# USB_Type-C_Test.net
KiCad netlist of a schematic drawn in EAGLE
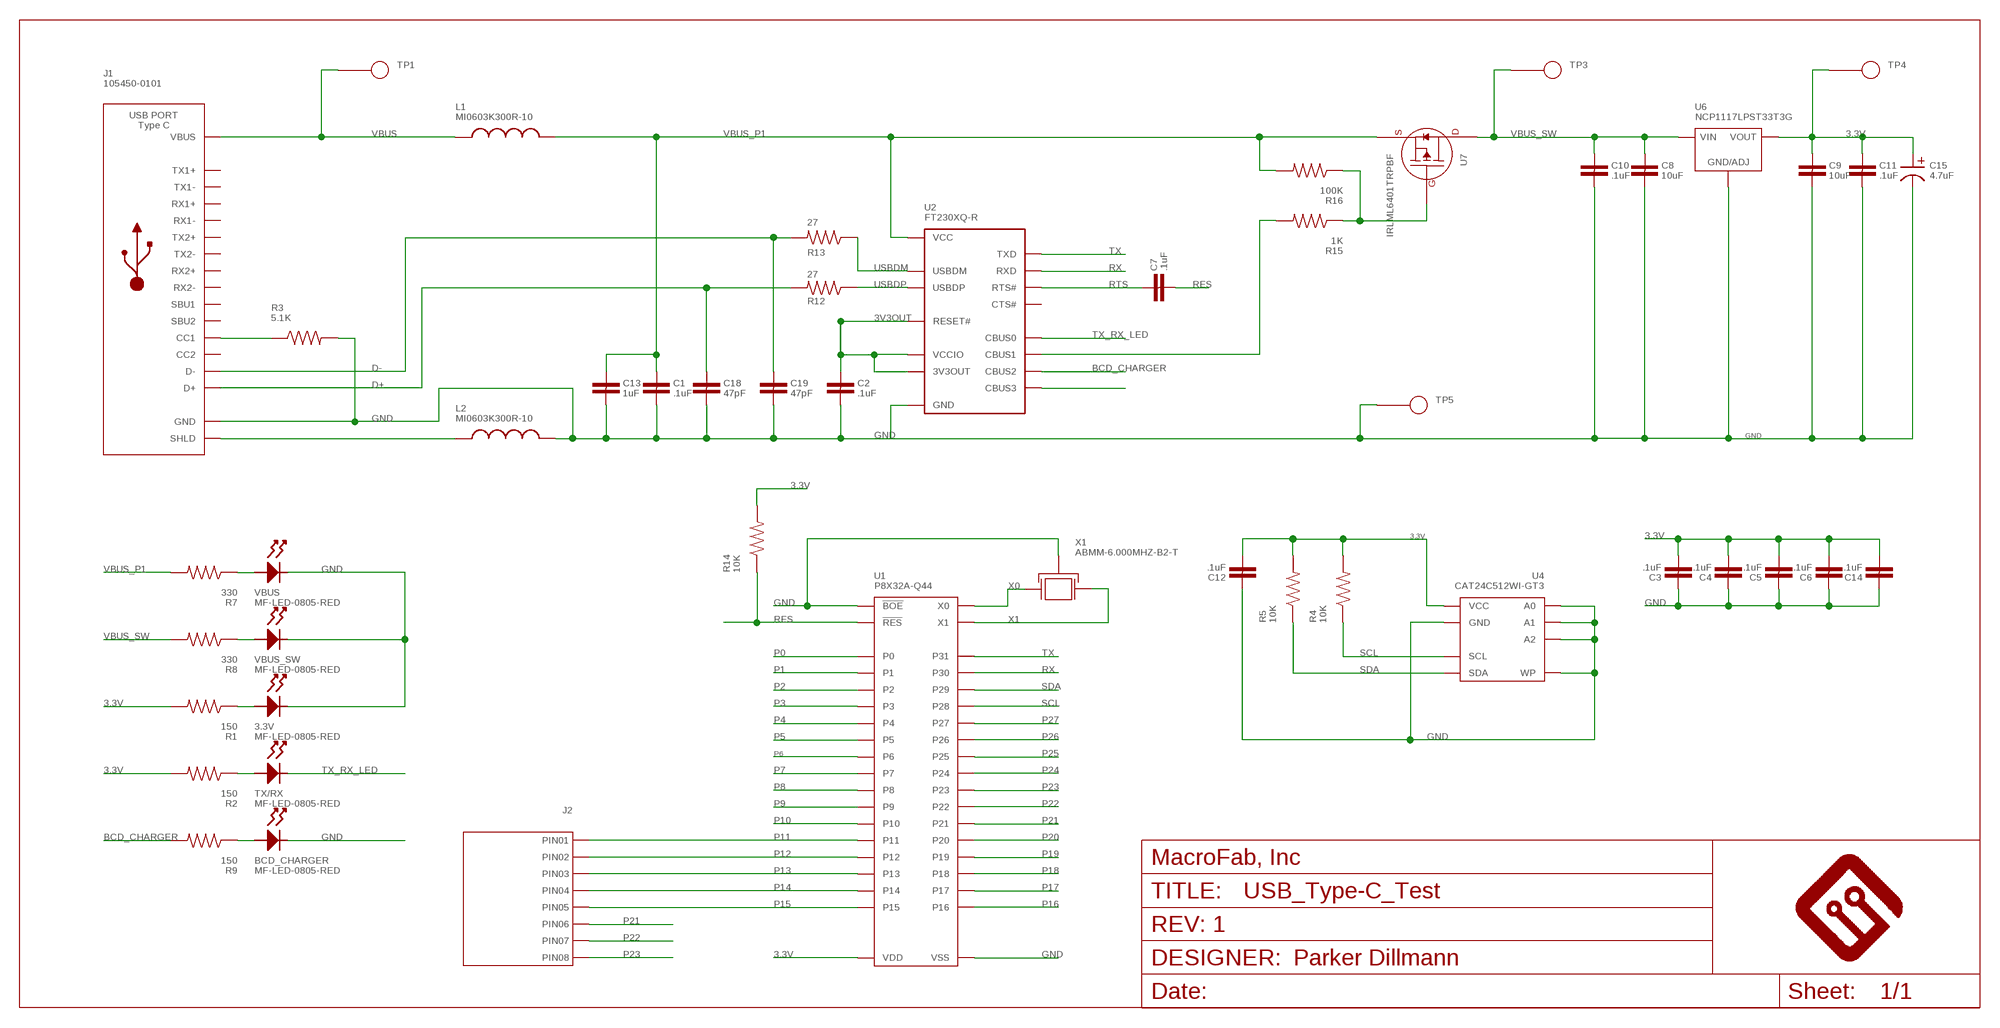
[diagram p0: schematic, sheet 1]

(export (version "E")
  (design (tool "Eeschema 10.0.6"))
  (components
    (comp (ref "3.3V")
      (value "MF-LED-0805-RED")
      (footprint "eagle-import:LED_0805")
      (libsource (lib "eagle-import") (part "LED_SINGLE_0805"))
    )
    (comp (ref "BCD_CHARGER")
      (value "MF-LED-0805-RED")
      (footprint "eagle-import:LED_0805")
      (libsource (lib "eagle-import") (part "LED_SINGLE_0805"))
    )
    (comp (ref "C1")
      (value ".1uF")
      (footprint "eagle-import:0603")
      (libsource (lib "eagle-import") (part "CAPACITOR_NON_POLAR_0603"))
    )
    (comp (ref "C2")
      (value ".1uF")
      (footprint "eagle-import:0603")
      (libsource (lib "eagle-import") (part "CAPACITOR_NON_POLAR_0603"))
    )
    (comp (ref "C3")
      (value ".1uF")
      (footprint "eagle-import:0603")
      (libsource (lib "eagle-import") (part "CAPACITOR_NON_POLAR_0603"))
    )
    (comp (ref "C4")
      (value ".1uF")
      (footprint "eagle-import:0603")
      (libsource (lib "eagle-import") (part "CAPACITOR_NON_POLAR_0603"))
    )
    (comp (ref "C5")
      (value ".1uF")
      (footprint "eagle-import:0603")
      (libsource (lib "eagle-import") (part "CAPACITOR_NON_POLAR_0603"))
    )
    (comp (ref "C6")
      (value ".1uF")
      (footprint "eagle-import:0603")
      (libsource (lib "eagle-import") (part "CAPACITOR_NON_POLAR_0603"))
    )
    (comp (ref "C7")
      (value ".1uF")
      (footprint "eagle-import:0603")
      (libsource (lib "eagle-import") (part "CAPACITOR_NON_POLAR_0603"))
    )
    (comp (ref "C8")
      (value "10uF")
      (footprint "eagle-import:1206")
      (libsource (lib "eagle-import") (part "CAPACITOR_NON_POLAR_1206"))
    )
    (comp (ref "C9")
      (value "10uF")
      (footprint "eagle-import:1206")
      (libsource (lib "eagle-import") (part "CAPACITOR_NON_POLAR_1206"))
    )
    (comp (ref "C10")
      (value ".1uF")
      (footprint "eagle-import:0603")
      (libsource (lib "eagle-import") (part "CAPACITOR_NON_POLAR_0603"))
    )
    (comp (ref "C11")
      (value ".1uF")
      (footprint "eagle-import:0603")
      (libsource (lib "eagle-import") (part "CAPACITOR_NON_POLAR_0603"))
    )
    (comp (ref "C12")
      (value ".1uF")
      (footprint "eagle-import:0603")
      (libsource (lib "eagle-import") (part "CAPACITOR_NON_POLAR_0603"))
    )
    (comp (ref "C13")
      (value "1uF")
      (footprint "eagle-import:0603")
      (libsource (lib "eagle-import") (part "CAPACITOR_NON_POLAR_0603"))
    )
    (comp (ref "C14")
      (value ".1uF")
      (footprint "eagle-import:0603")
      (libsource (lib "eagle-import") (part "CAPACITOR_NON_POLAR_0603"))
    )
    (comp (ref "C15")
      (value "4.7uF")
      (footprint "eagle-import:5MM_CAP_SMD")
      (libsource (lib "eagle-import") (part "CAPACITOR_POLARIZED_5MM_SMD"))
    )
    (comp (ref "C18")
      (value "47pF")
      (footprint "eagle-import:0603")
      (libsource (lib "eagle-import") (part "CAPACITOR_NON_POLAR_0603"))
    )
    (comp (ref "C19")
      (value "47pF")
      (footprint "eagle-import:0603")
      (libsource (lib "eagle-import") (part "CAPACITOR_NON_POLAR_0603"))
    )
    (comp (ref "FRAME1")
      (value "MF_FRAMEDEFAULT")
      (footprint "eagle-import:MF_FRAME_DEFAULT")
      (fields
        (field (name "HOUSEPART") "0")
        (field (name "DNAME") "Parker Dillmann")
        (field (name "REVNUM") "REV: 1")
      )
      (libsource (lib "eagle-import") (part "MF_FRAMEDEFAULT"))
    )
    (comp (ref "J1")
      (value "105450-0101")
      (footprint "eagle-import:105450-0101")
      (fields (field (name "MPN") "105450-0101"))
      (libsource (lib "eagle-import") (part "USB_TYPE-C_105450-0101"))
    )
    (comp (ref "J2")
      (value "CON_01X08_2.54MM_PIN_HEADER")
      (footprint "eagle-import:2.54MM_01X08_PIN_HEADER")
      (libsource (lib "eagle-import") (part "CON_01X08_2.54MM_PIN_HEADER"))
    )
    (comp (ref "L1")
      (value "MI0603K300R-10")
      (footprint "eagle-import:0603")
      (libsource (lib "eagle-import") (part "INDUCTOR_0603"))
    )
    (comp (ref "L2")
      (value "MI0603K300R-10")
      (footprint "eagle-import:0603")
      (libsource (lib "eagle-import") (part "INDUCTOR_0603"))
    )
    (comp (ref "R1")
      (value "150")
      (footprint "eagle-import:0603")
      (libsource (lib "eagle-import") (part "RESISTOR_0603"))
    )
    (comp (ref "R2")
      (value "150")
      (footprint "eagle-import:0603")
      (libsource (lib "eagle-import") (part "RESISTOR_0603"))
    )
    (comp (ref "R3")
      (value "5.1K")
      (footprint "eagle-import:0603")
      (libsource (lib "eagle-import") (part "RESISTOR_0603"))
    )
    (comp (ref "R4")
      (value "10K")
      (footprint "eagle-import:0603")
      (libsource (lib "eagle-import") (part "RESISTOR_0603"))
    )
    (comp (ref "R5")
      (value "10K")
      (footprint "eagle-import:0603")
      (libsource (lib "eagle-import") (part "RESISTOR_0603"))
    )
    (comp (ref "R7")
      (value "330")
      (footprint "eagle-import:0603")
      (libsource (lib "eagle-import") (part "RESISTOR_0603"))
    )
    (comp (ref "R8")
      (value "330")
      (footprint "eagle-import:0603")
      (libsource (lib "eagle-import") (part "RESISTOR_0603"))
    )
    (comp (ref "R9")
      (value "150")
      (footprint "eagle-import:0603")
      (libsource (lib "eagle-import") (part "RESISTOR_0603"))
    )
    (comp (ref "R12")
      (value "27")
      (footprint "eagle-import:0603")
      (libsource (lib "eagle-import") (part "RESISTOR_0603"))
    )
    (comp (ref "R13")
      (value "27")
      (footprint "eagle-import:0603")
      (libsource (lib "eagle-import") (part "RESISTOR_0603"))
    )
    (comp (ref "R14")
      (value "10K")
      (footprint "eagle-import:0603")
      (libsource (lib "eagle-import") (part "RESISTOR_0603"))
    )
    (comp (ref "R15")
      (value "1K")
      (footprint "eagle-import:0603")
      (libsource (lib "eagle-import") (part "RESISTOR_0603"))
    )
    (comp (ref "R16")
      (value "100K")
      (footprint "eagle-import:0603")
      (libsource (lib "eagle-import") (part "RESISTOR_0603"))
    )
    (comp (ref "TP1")
      (value "TEST_POINT_SINGLE_KEYSTONE_5115-5119")
      (footprint "eagle-import:KEYSTONE_5115-5119")
      (libsource (lib "eagle-import") (part "TEST_POINT_SINGLE_KEYSTONE_5115-5119"))
    )
    (comp (ref "TP3")
      (value "TEST_POINT_SINGLE_KEYSTONE_5115-5119")
      (footprint "eagle-import:KEYSTONE_5115-5119")
      (libsource (lib "eagle-import") (part "TEST_POINT_SINGLE_KEYSTONE_5115-5119"))
    )
    (comp (ref "TP4")
      (value "TEST_POINT_SINGLE_KEYSTONE_5115-5119")
      (footprint "eagle-import:KEYSTONE_5115-5119")
      (libsource (lib "eagle-import") (part "TEST_POINT_SINGLE_KEYSTONE_5115-5119"))
    )
    (comp (ref "TP5")
      (value "TEST_POINT_SINGLE_KEYSTONE_5115-5119")
      (footprint "eagle-import:KEYSTONE_5115-5119")
      (libsource (lib "eagle-import") (part "TEST_POINT_SINGLE_KEYSTONE_5115-5119"))
    )
    (comp (ref "TX/RX")
      (value "MF-LED-0805-RED")
      (footprint "eagle-import:LED_0805")
      (libsource (lib "eagle-import") (part "LED_SINGLE_0805"))
    )
    (comp (ref "U1")
      (value "P8X32A-Q44")
      (footprint "eagle-import:P8X32A_LQFP-44")
      (libsource (lib "eagle-import") (part "P8X32A-Q44"))
    )
    (comp (ref "U2")
      (value "FT230XQ-R")
      (footprint "eagle-import:FT230X_QFN-16")
      (libsource (lib "eagle-import") (part "FT230XQ"))
    )
    (comp (ref "U4")
      (value "CAT24C512WI-GT3")
      (footprint "eagle-import:SOIC-8_W")
      (libsource (lib "eagle-import") (part "EEPROM_I2CSOIC-8_W"))
    )
    (comp (ref "U6")
      (value "NCP1117LPST33T3G")
      (footprint "eagle-import:SOT-223-3")
      (fields (field (name "HOUSEPART") "NO"))
      (libsource (lib "eagle-import") (part "NCP1117LPST33T3G"))
    )
    (comp (ref "U7")
      (value "IRLML6401TRPBF")
      (footprint "eagle-import:SOT-23-3")
      (libsource (lib "eagle-import") (part "MOSFET_P-CHANNEL_SINGLE_SOT-23"))
    )
    (comp (ref "VBUS")
      (value "MF-LED-0805-RED")
      (footprint "eagle-import:LED_0805")
      (libsource (lib "eagle-import") (part "LED_SINGLE_0805"))
    )
    (comp (ref "VBUS_SW")
      (value "MF-LED-0805-RED")
      (footprint "eagle-import:LED_0805")
      (libsource (lib "eagle-import") (part "LED_SINGLE_0805"))
    )
    (comp (ref "X1")
      (value "ABMM-6.000MHZ-B2-T")
      (footprint "eagle-import:7MMX5MM")
      (fields (field (name "HOUSEPART") "NO"))
      (libsource (lib "eagle-import") (part "CYRSTAL_GND_ABMM"))
    )
  )
  (nets
    (net (code "1") (name "/3.3V") (class "Default")
      (node (ref "C11") (pin "1") (pinfunction "1_1") (pintype "passive"))
      (node (ref "C12") (pin "2") (pinfunction "2_2") (pintype "passive"))
      (node (ref "C14") (pin "2") (pinfunction "2_2") (pintype "passive"))
      (node (ref "C15") (pin "P") (pinfunction "POS_P") (pintype "bidirectional"))
      (node (ref "C3") (pin "2") (pinfunction "2_2") (pintype "passive"))
      (node (ref "C4") (pin "2") (pinfunction "2_2") (pintype "passive"))
      (node (ref "C5") (pin "2") (pinfunction "2_2") (pintype "passive"))
      (node (ref "C6") (pin "2") (pinfunction "2_2") (pintype "passive"))
      (node (ref "C9") (pin "1") (pinfunction "1_1") (pintype "passive"))
      (node (ref "R1") (pin "2") (pinfunction "2_2") (pintype "passive"))
      (node (ref "R14") (pin "2") (pinfunction "2_2") (pintype "passive"))
      (node (ref "R2") (pin "2") (pinfunction "2_2") (pintype "passive"))
      (node (ref "R4") (pin "2") (pinfunction "2_2") (pintype "passive"))
      (node (ref "R5") (pin "2") (pinfunction "2_2") (pintype "passive"))
      (node (ref "TP4") (pin "P$1") (pinfunction "P$1_P$1") (pintype "bidirectional"))
      (node (ref "U1") (pin "18") (pinfunction "VDD_18") (pintype "bidirectional"))
      (node (ref "U1") (pin "30") (pinfunction "VDD_30") (pintype "bidirectional"))
      (node (ref "U1") (pin "40") (pinfunction "VDD_40") (pintype "bidirectional"))
      (node (ref "U1") (pin "8") (pinfunction "VDD_8") (pintype "bidirectional"))
      (node (ref "U4") (pin "8") (pinfunction "VCC_8") (pintype "bidirectional"))
      (node (ref "U6") (pin "P$1") (pinfunction "VOUT_P$1") (pintype "bidirectional"))
      (node (ref "U6") (pin "P$3") (pinfunction "VOUT_P$3") (pintype "bidirectional"))
    )
    (net (code "2") (name "/3V3OUT") (class "Default")
      (node (ref "C2") (pin "1") (pinfunction "1_1") (pintype "passive"))
      (node (ref "U2") (pin "1") (pinfunction "VCCIO_1") (pintype "bidirectional"))
      (node (ref "U2") (pin "8") (pinfunction "3V3OUT_8") (pintype "bidirectional"))
      (node (ref "U2") (pin "9") (pinfunction "RESET#_9") (pintype "bidirectional"))
    )
    (net (code "3") (name "/BCD_CHARGER") (class "Default")
      (node (ref "R9") (pin "2") (pinfunction "2_2") (pintype "passive"))
      (node (ref "U2") (pin "5") (pinfunction "CBUS2_5") (pintype "bidirectional"))
    )
    (net (code "4") (name "/D+") (class "Default")
      (node (ref "C18") (pin "1") (pinfunction "1_1") (pintype "passive"))
      (node (ref "J1") (pin "A6") (pinfunction "D+_A6") (pintype "bidirectional"))
      (node (ref "J1") (pin "B6") (pinfunction "D+_B6") (pintype "bidirectional"))
      (node (ref "R12") (pin "2") (pinfunction "2_2") (pintype "passive"))
    )
    (net (code "5") (name "/D-") (class "Default")
      (node (ref "C19") (pin "1") (pinfunction "1_1") (pintype "passive"))
      (node (ref "J1") (pin "A7") (pinfunction "D-_A7") (pintype "bidirectional"))
      (node (ref "J1") (pin "B7") (pinfunction "D-_B7") (pintype "bidirectional"))
      (node (ref "R13") (pin "2") (pinfunction "2_2") (pintype "passive"))
    )
    (net (code "6") (name "/GND") (class "Default")
      (node (ref "3.3V") (pin "CATHODE") (pinfunction "CATHODE_CATHODE") (pintype "bidirectional"))
      (node (ref "BCD_CHARGER") (pin "CATHODE") (pinfunction "CATHODE_CATHODE") (pintype "bidirectional"))
      (node (ref "C1") (pin "2") (pinfunction "2_2") (pintype "passive"))
      (node (ref "C10") (pin "2") (pinfunction "2_2") (pintype "passive"))
      (node (ref "C11") (pin "2") (pinfunction "2_2") (pintype "passive"))
      (node (ref "C12") (pin "1") (pinfunction "1_1") (pintype "passive"))
      (node (ref "C13") (pin "2") (pinfunction "2_2") (pintype "passive"))
      (node (ref "C14") (pin "1") (pinfunction "1_1") (pintype "passive"))
      (node (ref "C15") (pin "N") (pinfunction "NEG_N") (pintype "bidirectional"))
      (node (ref "C18") (pin "2") (pinfunction "2_2") (pintype "passive"))
      (node (ref "C19") (pin "2") (pinfunction "2_2") (pintype "passive"))
      (node (ref "C2") (pin "2") (pinfunction "2_2") (pintype "passive"))
      (node (ref "C3") (pin "1") (pinfunction "1_1") (pintype "passive"))
      (node (ref "C4") (pin "1") (pinfunction "1_1") (pintype "passive"))
      (node (ref "C5") (pin "1") (pinfunction "1_1") (pintype "passive"))
      (node (ref "C6") (pin "1") (pinfunction "1_1") (pintype "passive"))
      (node (ref "C8") (pin "2") (pinfunction "2_2") (pintype "passive"))
      (node (ref "C9") (pin "2") (pinfunction "2_2") (pintype "passive"))
      (node (ref "J1") (pin "A1") (pinfunction "GND_A1") (pintype "bidirectional"))
      (node (ref "J1") (pin "A12") (pinfunction "GND_A12") (pintype "bidirectional"))
      (node (ref "J1") (pin "B1") (pinfunction "GND_B1") (pintype "bidirectional"))
      (node (ref "J1") (pin "B12") (pinfunction "GND_B12") (pintype "bidirectional"))
      (node (ref "L2") (pin "2") (pinfunction "P$2_2") (pintype "bidirectional"))
      (node (ref "R3") (pin "2") (pinfunction "2_2") (pintype "passive"))
      (node (ref "TP5") (pin "P$1") (pinfunction "P$1_P$1") (pintype "bidirectional"))
      (node (ref "U1") (pin "17") (pinfunction "VSS_17") (pintype "bidirectional"))
      (node (ref "U1") (pin "27") (pinfunction "VSS_27") (pintype "bidirectional"))
      (node (ref "U1") (pin "39") (pinfunction "VSS_39") (pintype "bidirectional"))
      (node (ref "U1") (pin "5") (pinfunction "VSS_5") (pintype "bidirectional"))
      (node (ref "U1") (pin "6") (pinfunction "~{BOE}_6") (pintype "bidirectional"))
      (node (ref "U2") (pin "13") (pinfunction "GND_13") (pintype "bidirectional"))
      (node (ref "U2") (pin "3") (pinfunction "GND_3") (pintype "bidirectional"))
      (node (ref "U2") (pin "PAD") (pinfunction "GND_PAD") (pintype "bidirectional"))
      (node (ref "U4") (pin "1") (pinfunction "A0_1") (pintype "bidirectional"))
      (node (ref "U4") (pin "2") (pinfunction "A1_2") (pintype "bidirectional"))
      (node (ref "U4") (pin "3") (pinfunction "A2_3") (pintype "bidirectional"))
      (node (ref "U4") (pin "4") (pinfunction "GND_4") (pintype "bidirectional"))
      (node (ref "U4") (pin "7") (pinfunction "WP_7") (pintype "bidirectional"))
      (node (ref "U6") (pin "P$2") (pinfunction "GND/ADJ_P$2") (pintype "bidirectional"))
      (node (ref "VBUS") (pin "CATHODE") (pinfunction "CATHODE_CATHODE") (pintype "bidirectional"))
      (node (ref "VBUS_SW") (pin "CATHODE") (pinfunction "CATHODE_CATHODE") (pintype "bidirectional"))
      (node (ref "X1") (pin "P$2") (pinfunction "GND_P$2") (pintype "bidirectional"))
      (node (ref "X1") (pin "P$4") (pinfunction "GND_P$4") (pintype "bidirectional"))
    )
    (net (code "7") (name "/P0") (class "Default")
      (node (ref "U1") (pin "41") (pinfunction "P0_41") (pintype "bidirectional"))
    )
    (net (code "8") (name "/P1") (class "Default")
      (node (ref "U1") (pin "42") (pinfunction "P1_42") (pintype "bidirectional"))
    )
    (net (code "9") (name "/P2") (class "Default")
      (node (ref "U1") (pin "43") (pinfunction "P2_43") (pintype "bidirectional"))
    )
    (net (code "10") (name "/P3") (class "Default")
      (node (ref "U1") (pin "44") (pinfunction "P3_44") (pintype "bidirectional"))
    )
    (net (code "11") (name "/P4") (class "Default")
      (node (ref "U1") (pin "1") (pinfunction "P4_1") (pintype "bidirectional"))
    )
    (net (code "12") (name "/P5") (class "Default")
      (node (ref "U1") (pin "2") (pinfunction "P5_2") (pintype "bidirectional"))
    )
    (net (code "13") (name "/P6") (class "Default")
      (node (ref "U1") (pin "3") (pinfunction "P6_3") (pintype "bidirectional"))
    )
    (net (code "14") (name "/P7") (class "Default")
      (node (ref "U1") (pin "4") (pinfunction "P7_4") (pintype "bidirectional"))
    )
    (net (code "15") (name "/P8") (class "Default")
      (node (ref "U1") (pin "9") (pinfunction "P8_9") (pintype "bidirectional"))
    )
    (net (code "16") (name "/P9") (class "Default")
      (node (ref "U1") (pin "10") (pinfunction "P9_10") (pintype "bidirectional"))
    )
    (net (code "17") (name "/P10") (class "Default")
      (node (ref "U1") (pin "11") (pinfunction "P10_11") (pintype "bidirectional"))
    )
    (net (code "18") (name "/P11") (class "Default")
      (node (ref "J2") (pin "1") (pinfunction "1_1") (pintype "bidirectional"))
      (node (ref "U1") (pin "12") (pinfunction "P11_12") (pintype "bidirectional"))
    )
    (net (code "19") (name "/P12") (class "Default")
      (node (ref "J2") (pin "2") (pinfunction "2_2") (pintype "bidirectional"))
      (node (ref "U1") (pin "13") (pinfunction "P12_13") (pintype "bidirectional"))
    )
    (net (code "20") (name "/P13") (class "Default")
      (node (ref "J2") (pin "3") (pinfunction "3_3") (pintype "bidirectional"))
      (node (ref "U1") (pin "14") (pinfunction "P13_14") (pintype "bidirectional"))
    )
    (net (code "21") (name "/P14") (class "Default")
      (node (ref "J2") (pin "4") (pinfunction "4_4") (pintype "bidirectional"))
      (node (ref "U1") (pin "15") (pinfunction "P14_15") (pintype "bidirectional"))
    )
    (net (code "22") (name "/P15") (class "Default")
      (node (ref "J2") (pin "5") (pinfunction "5_5") (pintype "bidirectional"))
      (node (ref "U1") (pin "16") (pinfunction "P15_16") (pintype "bidirectional"))
    )
    (net (code "23") (name "/P16") (class "Default")
      (node (ref "U1") (pin "19") (pinfunction "P16_19") (pintype "bidirectional"))
    )
    (net (code "24") (name "/P17") (class "Default")
      (node (ref "U1") (pin "20") (pinfunction "P17_20") (pintype "bidirectional"))
    )
    (net (code "25") (name "/P18") (class "Default")
      (node (ref "U1") (pin "21") (pinfunction "P18_21") (pintype "bidirectional"))
    )
    (net (code "26") (name "/P19") (class "Default")
      (node (ref "U1") (pin "22") (pinfunction "P19_22") (pintype "bidirectional"))
    )
    (net (code "27") (name "/P20") (class "Default")
      (node (ref "U1") (pin "23") (pinfunction "P20_23") (pintype "bidirectional"))
    )
    (net (code "28") (name "/P21") (class "Default")
      (node (ref "J2") (pin "6") (pinfunction "6_6") (pintype "bidirectional"))
      (node (ref "U1") (pin "24") (pinfunction "P21_24") (pintype "bidirectional"))
    )
    (net (code "29") (name "/P22") (class "Default")
      (node (ref "J2") (pin "7") (pinfunction "7_7") (pintype "bidirectional"))
      (node (ref "U1") (pin "25") (pinfunction "P22_25") (pintype "bidirectional"))
    )
    (net (code "30") (name "/P23") (class "Default")
      (node (ref "J2") (pin "8") (pinfunction "8_8") (pintype "bidirectional"))
      (node (ref "U1") (pin "26") (pinfunction "P23_26") (pintype "bidirectional"))
    )
    (net (code "31") (name "/P24") (class "Default")
      (node (ref "U1") (pin "31") (pinfunction "P24_31") (pintype "bidirectional"))
    )
    (net (code "32") (name "/P25") (class "Default")
      (node (ref "U1") (pin "32") (pinfunction "P25_32") (pintype "bidirectional"))
    )
    (net (code "33") (name "/P26") (class "Default")
      (node (ref "U1") (pin "33") (pinfunction "P26_33") (pintype "bidirectional"))
    )
    (net (code "34") (name "/P27") (class "Default")
      (node (ref "U1") (pin "34") (pinfunction "P27_34") (pintype "bidirectional"))
    )
    (net (code "35") (name "/RES") (class "Default")
      (node (ref "C7") (pin "2") (pinfunction "2_2") (pintype "passive"))
      (node (ref "R14") (pin "1") (pinfunction "1_1") (pintype "passive"))
      (node (ref "U1") (pin "7") (pinfunction "~{RES}_7") (pintype "bidirectional"))
    )
    (net (code "36") (name "/RTS") (class "Default")
      (node (ref "C7") (pin "1") (pinfunction "1_1") (pintype "passive"))
      (node (ref "U2") (pin "16") (pinfunction "RTS#_16") (pintype "bidirectional"))
    )
    (net (code "37") (name "/RX") (class "Default")
      (node (ref "U1") (pin "37") (pinfunction "P30_37") (pintype "bidirectional"))
      (node (ref "U2") (pin "2") (pinfunction "RXD_2") (pintype "bidirectional"))
    )
    (net (code "38") (name "/SCL") (class "Default")
      (node (ref "R4") (pin "1") (pinfunction "1_1") (pintype "passive"))
      (node (ref "U1") (pin "35") (pinfunction "P28_35") (pintype "bidirectional"))
      (node (ref "U4") (pin "6") (pinfunction "SCL_6") (pintype "bidirectional"))
    )
    (net (code "39") (name "/SDA") (class "Default")
      (node (ref "R5") (pin "1") (pinfunction "1_1") (pintype "passive"))
      (node (ref "U1") (pin "36") (pinfunction "P29_36") (pintype "bidirectional"))
      (node (ref "U4") (pin "5") (pinfunction "SDA_5") (pintype "bidirectional"))
    )
    (net (code "40") (name "/TX") (class "Default")
      (node (ref "U1") (pin "38") (pinfunction "P31_38") (pintype "bidirectional"))
      (node (ref "U2") (pin "15") (pinfunction "TXD_15") (pintype "bidirectional"))
    )
    (net (code "41") (name "/TX_RX_LED") (class "Default")
      (node (ref "TX/RX") (pin "CATHODE") (pinfunction "CATHODE_CATHODE") (pintype "bidirectional"))
      (node (ref "U2") (pin "12") (pinfunction "CBUS0_12") (pintype "bidirectional"))
    )
    (net (code "42") (name "/USBDM") (class "Default")
      (node (ref "R13") (pin "1") (pinfunction "1_1") (pintype "passive"))
      (node (ref "U2") (pin "7") (pinfunction "USBDM_7") (pintype "bidirectional"))
    )
    (net (code "43") (name "/USBDP") (class "Default")
      (node (ref "R12") (pin "1") (pinfunction "1_1") (pintype "passive"))
      (node (ref "U2") (pin "6") (pinfunction "USBDP_6") (pintype "bidirectional"))
    )
    (net (code "44") (name "/VBUS") (class "Default")
      (node (ref "J1") (pin "A4") (pinfunction "VBUS_A4") (pintype "bidirectional"))
      (node (ref "J1") (pin "A9") (pinfunction "VBUS_A9") (pintype "bidirectional"))
      (node (ref "J1") (pin "B4") (pinfunction "VBUS_B4") (pintype "bidirectional"))
      (node (ref "J1") (pin "B9") (pinfunction "VBUS_B9") (pintype "bidirectional"))
      (node (ref "L1") (pin "1") (pinfunction "P$1_1") (pintype "bidirectional"))
      (node (ref "TP1") (pin "P$1") (pinfunction "P$1_P$1") (pintype "bidirectional"))
    )
    (net (code "45") (name "/VBUS_P1") (class "Default")
      (node (ref "C1") (pin "1") (pinfunction "1_1") (pintype "passive"))
      (node (ref "C13") (pin "1") (pinfunction "1_1") (pintype "passive"))
      (node (ref "L1") (pin "2") (pinfunction "P$2_2") (pintype "bidirectional"))
      (node (ref "R16") (pin "2") (pinfunction "2_2") (pintype "passive"))
      (node (ref "R7") (pin "2") (pinfunction "2_2") (pintype "passive"))
      (node (ref "U2") (pin "10") (pinfunction "VCC_10") (pintype "bidirectional"))
      (node (ref "U7") (pin "2") (pinfunction "SOURCE_2") (pintype "bidirectional"))
    )
    (net (code "46") (name "/VBUS_SW") (class "Default")
      (node (ref "C10") (pin "1") (pinfunction "1_1") (pintype "passive"))
      (node (ref "C8") (pin "1") (pinfunction "1_1") (pintype "passive"))
      (node (ref "R8") (pin "2") (pinfunction "2_2") (pintype "passive"))
      (node (ref "TP3") (pin "P$1") (pinfunction "P$1_P$1") (pintype "bidirectional"))
      (node (ref "U6") (pin "P$4") (pinfunction "VIN_P$4") (pintype "bidirectional"))
      (node (ref "U7") (pin "3") (pinfunction "DRAIN_3") (pintype "bidirectional"))
    )
    (net (code "47") (name "/X0") (class "Default")
      (node (ref "U1") (pin "29") (pinfunction "X0_29") (pintype "bidirectional"))
      (node (ref "X1") (pin "P$3") (pinfunction "X1_P$3") (pintype "bidirectional"))
    )
    (net (code "48") (name "/X1") (class "Default")
      (node (ref "U1") (pin "28") (pinfunction "X1_28") (pintype "bidirectional"))
      (node (ref "X1") (pin "P$1") (pinfunction "X0_P$1") (pintype "bidirectional"))
    )
    (net (code "49") (name "Net-(3.3V-PadANODE)") (class "Default")
      (node (ref "3.3V") (pin "ANODE") (pinfunction "ANODE_ANODE") (pintype "bidirectional"))
      (node (ref "R1") (pin "1") (pinfunction "1_1") (pintype "passive"))
    )
    (net (code "50") (name "Net-(BCD_CHARGER-PadANODE)") (class "Default")
      (node (ref "BCD_CHARGER") (pin "ANODE") (pinfunction "ANODE_ANODE") (pintype "bidirectional"))
      (node (ref "R9") (pin "1") (pinfunction "1_1") (pintype "passive"))
    )
    (net (code "51") (name "Net-(J1-CC1)") (class "Default")
      (node (ref "J1") (pin "A5") (pinfunction "CC1_A5") (pintype "bidirectional"))
      (node (ref "R3") (pin "1") (pinfunction "1_1") (pintype "passive"))
    )
    (net (code "52") (name "Net-(L2-P$1)") (class "Default")
      (node (ref "J1") (pin "S_T1") (pinfunction "SHLD_S_T1") (pintype "bidirectional"))
      (node (ref "J1") (pin "S_T2") (pinfunction "SHLD_S_T2") (pintype "bidirectional"))
      (node (ref "J1") (pin "S_T3") (pinfunction "SHLD_S_T3") (pintype "bidirectional"))
      (node (ref "J1") (pin "S_T4") (pinfunction "SHLD_S_T4") (pintype "bidirectional"))
      (node (ref "L2") (pin "1") (pinfunction "P$1_1") (pintype "bidirectional"))
    )
    (net (code "53") (name "Net-(R2-Pad1)") (class "Default")
      (node (ref "R2") (pin "1") (pinfunction "1_1") (pintype "passive"))
      (node (ref "TX/RX") (pin "ANODE") (pinfunction "ANODE_ANODE") (pintype "bidirectional"))
    )
    (net (code "54") (name "Net-(R7-Pad1)") (class "Default")
      (node (ref "R7") (pin "1") (pinfunction "1_1") (pintype "passive"))
      (node (ref "VBUS") (pin "ANODE") (pinfunction "ANODE_ANODE") (pintype "bidirectional"))
    )
    (net (code "55") (name "Net-(R8-Pad1)") (class "Default")
      (node (ref "R8") (pin "1") (pinfunction "1_1") (pintype "passive"))
      (node (ref "VBUS_SW") (pin "ANODE") (pinfunction "ANODE_ANODE") (pintype "bidirectional"))
    )
    (net (code "56") (name "Net-(U2-CBUS1)") (class "Default")
      (node (ref "R15") (pin "2") (pinfunction "2_2") (pintype "passive"))
      (node (ref "U2") (pin "11") (pinfunction "CBUS1_11") (pintype "bidirectional"))
    )
    (net (code "57") (name "Net-(U7-GATE)") (class "Default")
      (node (ref "R15") (pin "1") (pinfunction "1_1") (pintype "passive"))
      (node (ref "R16") (pin "1") (pinfunction "1_1") (pintype "passive"))
      (node (ref "U7") (pin "1") (pinfunction "GATE_1") (pintype "bidirectional"))
    )
    (net (code "58") (name "unconnected-(J1-CC2-PadB5)") (class "Default")
      (node (ref "J1") (pin "B5") (pinfunction "CC2_B5") (pintype "bidirectional"))
    )
    (net (code "59") (name "unconnected-(J1-RX1+-PadB11)") (class "Default")
      (node (ref "J1") (pin "B11") (pinfunction "RX1+_B11") (pintype "bidirectional"))
    )
    (net (code "60") (name "unconnected-(J1-RX1--PadB10)") (class "Default")
      (node (ref "J1") (pin "B10") (pinfunction "RX1-_B10") (pintype "bidirectional"))
    )
    (net (code "61") (name "unconnected-(J1-RX2+-PadA11)") (class "Default")
      (node (ref "J1") (pin "A11") (pinfunction "RX2+_A11") (pintype "bidirectional"))
    )
    (net (code "62") (name "unconnected-(J1-RX2--PadA10)") (class "Default")
      (node (ref "J1") (pin "A10") (pinfunction "RX2-_A10") (pintype "bidirectional"))
    )
    (net (code "63") (name "unconnected-(J1-SBU1-PadA8)") (class "Default")
      (node (ref "J1") (pin "A8") (pinfunction "SBU1_A8") (pintype "bidirectional"))
    )
    (net (code "64") (name "unconnected-(J1-SBU2-PadB8)") (class "Default")
      (node (ref "J1") (pin "B8") (pinfunction "SBU2_B8") (pintype "bidirectional"))
    )
    (net (code "65") (name "unconnected-(J1-TX1+-PadA2)") (class "Default")
      (node (ref "J1") (pin "A2") (pinfunction "TX1+_A2") (pintype "bidirectional"))
    )
    (net (code "66") (name "unconnected-(J1-TX1--PadA3)") (class "Default")
      (node (ref "J1") (pin "A3") (pinfunction "TX1-_A3") (pintype "bidirectional"))
    )
    (net (code "67") (name "unconnected-(J1-TX2+-PadB2)") (class "Default")
      (node (ref "J1") (pin "B2") (pinfunction "TX2+_B2") (pintype "bidirectional"))
    )
    (net (code "68") (name "unconnected-(J1-TX2--PadB3)") (class "Default")
      (node (ref "J1") (pin "B3") (pinfunction "TX2-_B3") (pintype "bidirectional"))
    )
    (net (code "69") (name "unconnected-(U2-CBUS3-Pad14)") (class "Default")
      (node (ref "U2") (pin "14") (pinfunction "CBUS3_14") (pintype "bidirectional"))
    )
    (net (code "70") (name "unconnected-(U2-CTS#-Pad4)") (class "Default")
      (node (ref "U2") (pin "4") (pinfunction "CTS#_4") (pintype "bidirectional"))
    )
  )
)
